# ArduSatPrototypingModule.net
KiCad netlist of a schematic drawn in EAGLE
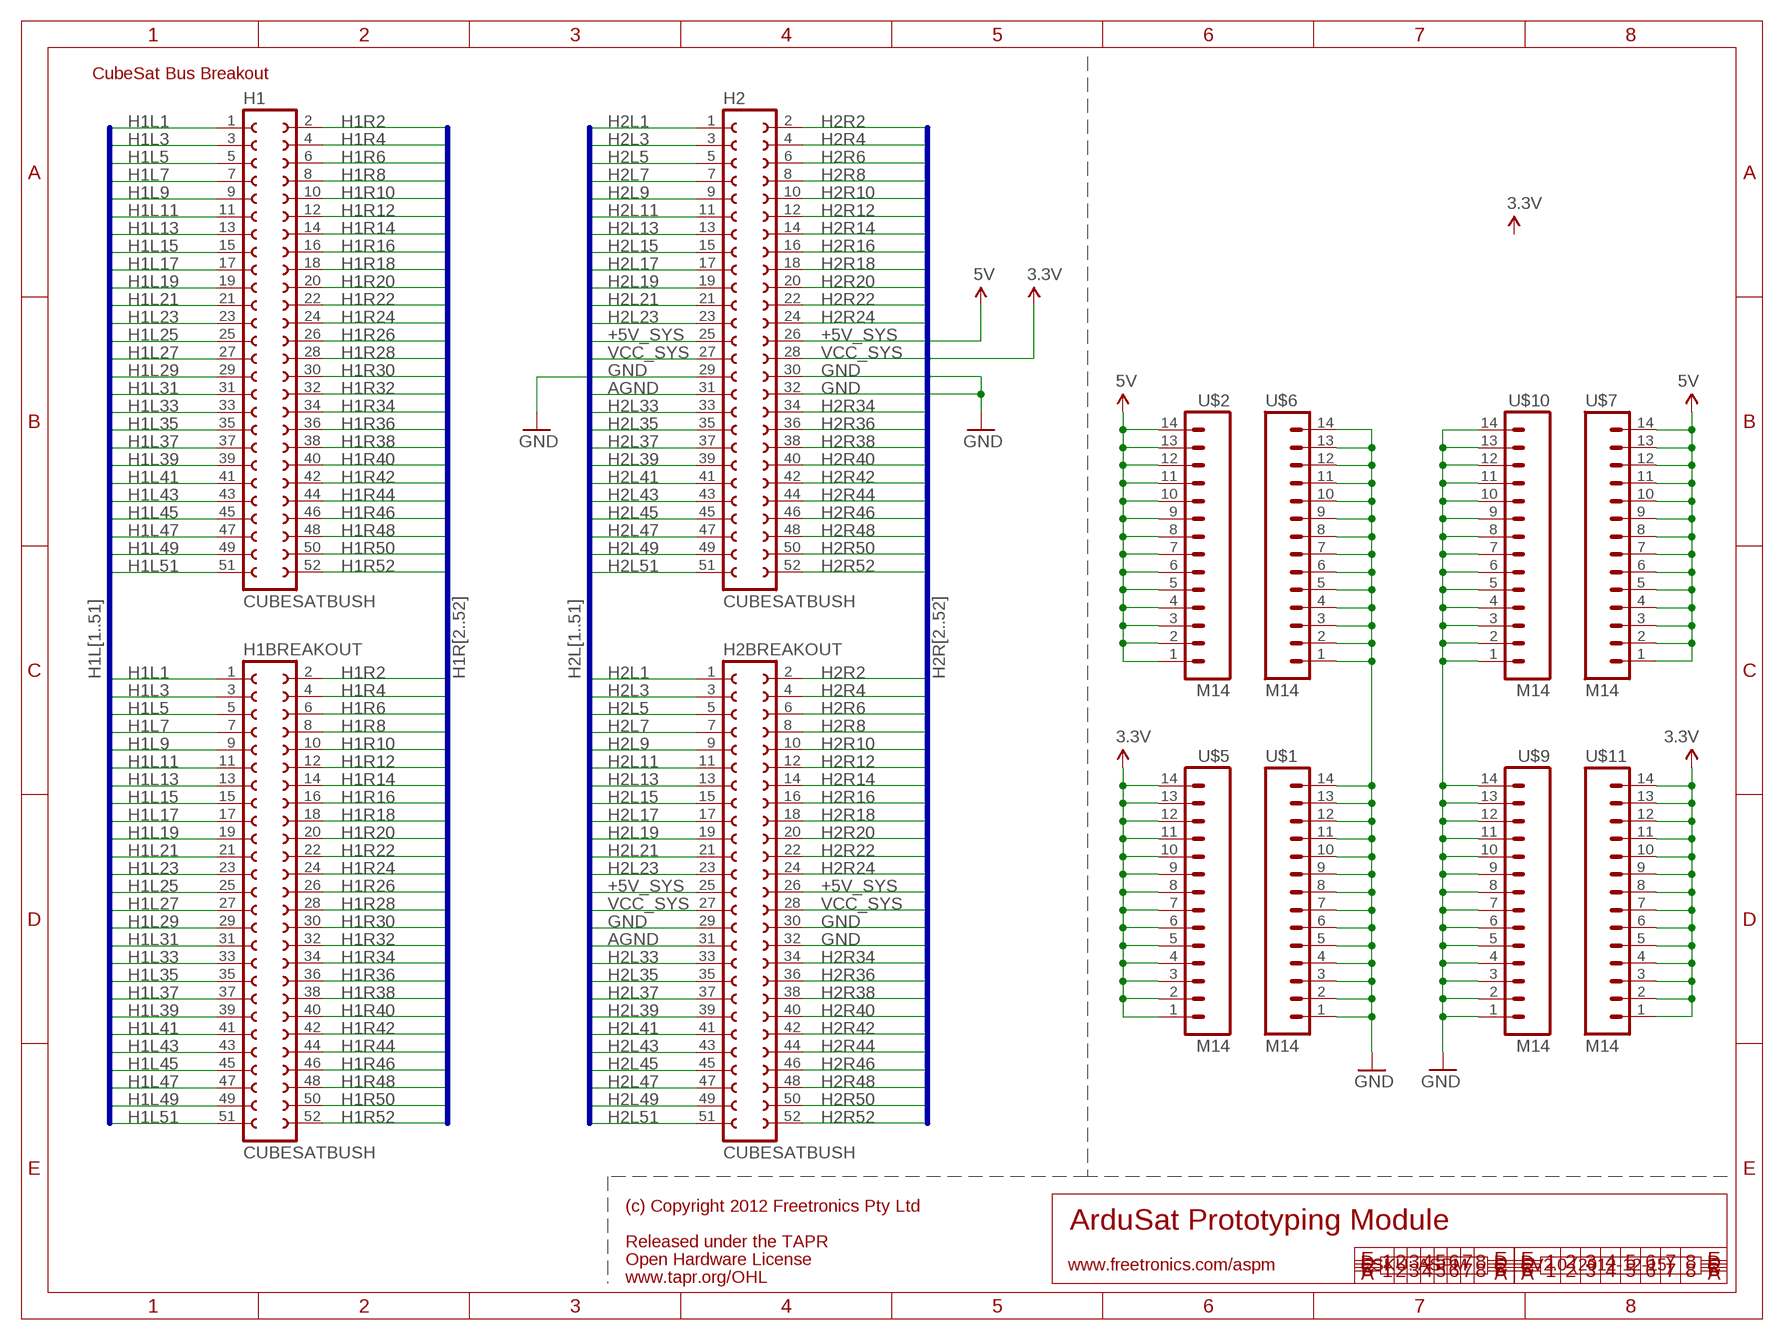
[diagram p0: schematic, sheet 1]

(export (version "E")
  (design (tool "Eeschema 10.0.6"))
  (components
    (comp (ref "H1")
      (value "CUBESATBUSH")
      (footprint "eagle-import:CUBESATBUS")
      (libsource (lib "eagle-import") (part "CUBESATBUSH"))
    )
    (comp (ref "H1BREAKOUT")
      (value "CUBESATBUSH")
      (footprint "eagle-import:CUBESATBUS")
      (libsource (lib "eagle-import") (part "CUBESATBUSH"))
    )
    (comp (ref "H2")
      (value "CUBESATBUSH")
      (footprint "eagle-import:CUBESATBUS")
      (libsource (lib "eagle-import") (part "CUBESATBUSH"))
    )
    (comp (ref "H2BREAKOUT")
      (value "CUBESATBUSH")
      (footprint "eagle-import:CUBESATBUS")
      (libsource (lib "eagle-import") (part "CUBESATBUSH"))
    )
    (comp (ref "U$1")
      (value "M14")
      (footprint "eagle-import:1X14")
      (libsource (lib "eagle-import") (part "M14"))
    )
    (comp (ref "U$2")
      (value "M14")
      (footprint "eagle-import:1X14")
      (libsource (lib "eagle-import") (part "M14"))
    )
    (comp (ref "U$5")
      (value "M14")
      (footprint "eagle-import:1X14")
      (libsource (lib "eagle-import") (part "M14"))
    )
    (comp (ref "U$6")
      (value "M14")
      (footprint "eagle-import:1X14")
      (libsource (lib "eagle-import") (part "M14"))
    )
    (comp (ref "U$7")
      (value "M14")
      (footprint "eagle-import:1X14")
      (libsource (lib "eagle-import") (part "M14"))
    )
    (comp (ref "U$9")
      (value "M14")
      (footprint "eagle-import:1X14")
      (libsource (lib "eagle-import") (part "M14"))
    )
    (comp (ref "U$10")
      (value "M14")
      (footprint "eagle-import:1X14")
      (libsource (lib "eagle-import") (part "M14"))
    )
    (comp (ref "U$11")
      (value "M14")
      (footprint "eagle-import:1X14")
      (libsource (lib "eagle-import") (part "M14"))
    )
  )
  (nets
    (net (code "109") (name "/AGND") (class "Default")
      (node (ref "H2") (pin "31") (pinfunction "31_31") (pintype "passive"))
      (node (ref "H2BREAKOUT") (pin "31") (pinfunction "31_31") (pintype "passive"))
    )
    (net (code "110") (name "/H1L1") (class "Default")
      (node (ref "H1") (pin "1") (pinfunction "1_1") (pintype "passive"))
      (node (ref "H1BREAKOUT") (pin "1") (pinfunction "1_1") (pintype "passive"))
    )
    (net (code "111") (name "/H1L3") (class "Default")
      (node (ref "H1") (pin "3") (pinfunction "3_3") (pintype "passive"))
      (node (ref "H1BREAKOUT") (pin "3") (pinfunction "3_3") (pintype "passive"))
    )
    (net (code "112") (name "/H1L5") (class "Default")
      (node (ref "H1") (pin "5") (pinfunction "5_5") (pintype "passive"))
      (node (ref "H1BREAKOUT") (pin "5") (pinfunction "5_5") (pintype "passive"))
    )
    (net (code "113") (name "/H1L7") (class "Default")
      (node (ref "H1") (pin "7") (pinfunction "7_7") (pintype "passive"))
      (node (ref "H1BREAKOUT") (pin "7") (pinfunction "7_7") (pintype "passive"))
    )
    (net (code "114") (name "/H1L9") (class "Default")
      (node (ref "H1") (pin "9") (pinfunction "9_9") (pintype "passive"))
      (node (ref "H1BREAKOUT") (pin "9") (pinfunction "9_9") (pintype "passive"))
    )
    (net (code "115") (name "/H1L11") (class "Default")
      (node (ref "H1") (pin "11") (pinfunction "11_11") (pintype "passive"))
      (node (ref "H1BREAKOUT") (pin "11") (pinfunction "11_11") (pintype "passive"))
    )
    (net (code "116") (name "/H1L13") (class "Default")
      (node (ref "H1") (pin "13") (pinfunction "13_13") (pintype "passive"))
      (node (ref "H1BREAKOUT") (pin "13") (pinfunction "13_13") (pintype "passive"))
    )
    (net (code "117") (name "/H1L15") (class "Default")
      (node (ref "H1") (pin "15") (pinfunction "15_15") (pintype "passive"))
      (node (ref "H1BREAKOUT") (pin "15") (pinfunction "15_15") (pintype "passive"))
    )
    (net (code "118") (name "/H1L17") (class "Default")
      (node (ref "H1") (pin "17") (pinfunction "17_17") (pintype "passive"))
      (node (ref "H1BREAKOUT") (pin "17") (pinfunction "17_17") (pintype "passive"))
    )
    (net (code "119") (name "/H1L19") (class "Default")
      (node (ref "H1") (pin "19") (pinfunction "19_19") (pintype "passive"))
      (node (ref "H1BREAKOUT") (pin "19") (pinfunction "19_19") (pintype "passive"))
    )
    (net (code "120") (name "/H1L21") (class "Default")
      (node (ref "H1") (pin "21") (pinfunction "21_21") (pintype "passive"))
      (node (ref "H1BREAKOUT") (pin "21") (pinfunction "21_21") (pintype "passive"))
    )
    (net (code "121") (name "/H1L23") (class "Default")
      (node (ref "H1") (pin "23") (pinfunction "23_23") (pintype "passive"))
      (node (ref "H1BREAKOUT") (pin "23") (pinfunction "23_23") (pintype "passive"))
    )
    (net (code "122") (name "/H1L25") (class "Default")
      (node (ref "H1") (pin "25") (pinfunction "25_25") (pintype "passive"))
      (node (ref "H1BREAKOUT") (pin "25") (pinfunction "25_25") (pintype "passive"))
    )
    (net (code "123") (name "/H1L27") (class "Default")
      (node (ref "H1") (pin "27") (pinfunction "27_27") (pintype "passive"))
      (node (ref "H1BREAKOUT") (pin "27") (pinfunction "27_27") (pintype "passive"))
    )
    (net (code "124") (name "/H1L29") (class "Default")
      (node (ref "H1") (pin "29") (pinfunction "29_29") (pintype "passive"))
      (node (ref "H1BREAKOUT") (pin "29") (pinfunction "29_29") (pintype "passive"))
    )
    (net (code "125") (name "/H1L31") (class "Default")
      (node (ref "H1") (pin "31") (pinfunction "31_31") (pintype "passive"))
      (node (ref "H1BREAKOUT") (pin "31") (pinfunction "31_31") (pintype "passive"))
    )
    (net (code "126") (name "/H1L33") (class "Default")
      (node (ref "H1") (pin "33") (pinfunction "33_33") (pintype "passive"))
      (node (ref "H1BREAKOUT") (pin "33") (pinfunction "33_33") (pintype "passive"))
    )
    (net (code "127") (name "/H1L35") (class "Default")
      (node (ref "H1") (pin "35") (pinfunction "35_35") (pintype "passive"))
      (node (ref "H1BREAKOUT") (pin "35") (pinfunction "35_35") (pintype "passive"))
    )
    (net (code "128") (name "/H1L37") (class "Default")
      (node (ref "H1") (pin "37") (pinfunction "37_37") (pintype "passive"))
      (node (ref "H1BREAKOUT") (pin "37") (pinfunction "37_37") (pintype "passive"))
    )
    (net (code "129") (name "/H1L39") (class "Default")
      (node (ref "H1") (pin "39") (pinfunction "39_39") (pintype "passive"))
      (node (ref "H1BREAKOUT") (pin "39") (pinfunction "39_39") (pintype "passive"))
    )
    (net (code "130") (name "/H1L41") (class "Default")
      (node (ref "H1") (pin "41") (pinfunction "41_41") (pintype "passive"))
      (node (ref "H1BREAKOUT") (pin "41") (pinfunction "41_41") (pintype "passive"))
    )
    (net (code "131") (name "/H1L43") (class "Default")
      (node (ref "H1") (pin "43") (pinfunction "43_43") (pintype "passive"))
      (node (ref "H1BREAKOUT") (pin "43") (pinfunction "43_43") (pintype "passive"))
    )
    (net (code "132") (name "/H1L45") (class "Default")
      (node (ref "H1") (pin "45") (pinfunction "45_45") (pintype "passive"))
      (node (ref "H1BREAKOUT") (pin "45") (pinfunction "45_45") (pintype "passive"))
    )
    (net (code "133") (name "/H1L47") (class "Default")
      (node (ref "H1") (pin "47") (pinfunction "47_47") (pintype "passive"))
      (node (ref "H1BREAKOUT") (pin "47") (pinfunction "47_47") (pintype "passive"))
    )
    (net (code "134") (name "/H1L49") (class "Default")
      (node (ref "H1") (pin "49") (pinfunction "49_49") (pintype "passive"))
      (node (ref "H1BREAKOUT") (pin "49") (pinfunction "49_49") (pintype "passive"))
    )
    (net (code "135") (name "/H1L51") (class "Default")
      (node (ref "H1") (pin "51") (pinfunction "51_51") (pintype "passive"))
      (node (ref "H1BREAKOUT") (pin "51") (pinfunction "51_51") (pintype "passive"))
    )
    (net (code "137") (name "/H1R2") (class "Default")
      (node (ref "H1") (pin "2") (pinfunction "2_2") (pintype "passive"))
      (node (ref "H1BREAKOUT") (pin "2") (pinfunction "2_2") (pintype "passive"))
    )
    (net (code "138") (name "/H1R4") (class "Default")
      (node (ref "H1") (pin "4") (pinfunction "4_4") (pintype "passive"))
      (node (ref "H1BREAKOUT") (pin "4") (pinfunction "4_4") (pintype "passive"))
    )
    (net (code "139") (name "/H1R6") (class "Default")
      (node (ref "H1") (pin "6") (pinfunction "6_6") (pintype "passive"))
      (node (ref "H1BREAKOUT") (pin "6") (pinfunction "6_6") (pintype "passive"))
    )
    (net (code "140") (name "/H1R8") (class "Default")
      (node (ref "H1") (pin "8") (pinfunction "8_8") (pintype "passive"))
      (node (ref "H1BREAKOUT") (pin "8") (pinfunction "8_8") (pintype "passive"))
    )
    (net (code "141") (name "/H1R10") (class "Default")
      (node (ref "H1") (pin "10") (pinfunction "10_10") (pintype "passive"))
      (node (ref "H1BREAKOUT") (pin "10") (pinfunction "10_10") (pintype "passive"))
    )
    (net (code "142") (name "/H1R12") (class "Default")
      (node (ref "H1") (pin "12") (pinfunction "12_12") (pintype "passive"))
      (node (ref "H1BREAKOUT") (pin "12") (pinfunction "12_12") (pintype "passive"))
    )
    (net (code "143") (name "/H1R14") (class "Default")
      (node (ref "H1") (pin "14") (pinfunction "14_14") (pintype "passive"))
      (node (ref "H1BREAKOUT") (pin "14") (pinfunction "14_14") (pintype "passive"))
    )
    (net (code "144") (name "/H1R16") (class "Default")
      (node (ref "H1") (pin "16") (pinfunction "16_16") (pintype "passive"))
      (node (ref "H1BREAKOUT") (pin "16") (pinfunction "16_16") (pintype "passive"))
    )
    (net (code "145") (name "/H1R18") (class "Default")
      (node (ref "H1") (pin "18") (pinfunction "18_18") (pintype "passive"))
      (node (ref "H1BREAKOUT") (pin "18") (pinfunction "18_18") (pintype "passive"))
    )
    (net (code "146") (name "/H1R20") (class "Default")
      (node (ref "H1") (pin "20") (pinfunction "20_20") (pintype "passive"))
      (node (ref "H1BREAKOUT") (pin "20") (pinfunction "20_20") (pintype "passive"))
    )
    (net (code "147") (name "/H1R22") (class "Default")
      (node (ref "H1") (pin "22") (pinfunction "22_22") (pintype "passive"))
      (node (ref "H1BREAKOUT") (pin "22") (pinfunction "22_22") (pintype "passive"))
    )
    (net (code "148") (name "/H1R24") (class "Default")
      (node (ref "H1") (pin "24") (pinfunction "24_24") (pintype "passive"))
      (node (ref "H1BREAKOUT") (pin "24") (pinfunction "24_24") (pintype "passive"))
    )
    (net (code "149") (name "/H1R26") (class "Default")
      (node (ref "H1") (pin "26") (pinfunction "26_26") (pintype "passive"))
      (node (ref "H1BREAKOUT") (pin "26") (pinfunction "26_26") (pintype "passive"))
    )
    (net (code "150") (name "/H1R28") (class "Default")
      (node (ref "H1") (pin "28") (pinfunction "28_28") (pintype "passive"))
      (node (ref "H1BREAKOUT") (pin "28") (pinfunction "28_28") (pintype "passive"))
    )
    (net (code "151") (name "/H1R30") (class "Default")
      (node (ref "H1") (pin "30") (pinfunction "30_30") (pintype "passive"))
      (node (ref "H1BREAKOUT") (pin "30") (pinfunction "30_30") (pintype "passive"))
    )
    (net (code "152") (name "/H1R32") (class "Default")
      (node (ref "H1") (pin "32") (pinfunction "32_32") (pintype "passive"))
      (node (ref "H1BREAKOUT") (pin "32") (pinfunction "32_32") (pintype "passive"))
    )
    (net (code "153") (name "/H1R34") (class "Default")
      (node (ref "H1") (pin "34") (pinfunction "34_34") (pintype "passive"))
      (node (ref "H1BREAKOUT") (pin "34") (pinfunction "34_34") (pintype "passive"))
    )
    (net (code "154") (name "/H1R36") (class "Default")
      (node (ref "H1") (pin "36") (pinfunction "36_36") (pintype "passive"))
      (node (ref "H1BREAKOUT") (pin "36") (pinfunction "36_36") (pintype "passive"))
    )
    (net (code "155") (name "/H1R38") (class "Default")
      (node (ref "H1") (pin "38") (pinfunction "38_38") (pintype "passive"))
      (node (ref "H1BREAKOUT") (pin "38") (pinfunction "38_38") (pintype "passive"))
    )
    (net (code "156") (name "/H1R40") (class "Default")
      (node (ref "H1") (pin "40") (pinfunction "40_40") (pintype "passive"))
      (node (ref "H1BREAKOUT") (pin "40") (pinfunction "40_40") (pintype "passive"))
    )
    (net (code "157") (name "/H1R42") (class "Default")
      (node (ref "H1") (pin "42") (pinfunction "42_42") (pintype "passive"))
      (node (ref "H1BREAKOUT") (pin "42") (pinfunction "42_42") (pintype "passive"))
    )
    (net (code "158") (name "/H1R44") (class "Default")
      (node (ref "H1") (pin "44") (pinfunction "44_44") (pintype "passive"))
      (node (ref "H1BREAKOUT") (pin "44") (pinfunction "44_44") (pintype "passive"))
    )
    (net (code "159") (name "/H1R46") (class "Default")
      (node (ref "H1") (pin "46") (pinfunction "46_46") (pintype "passive"))
      (node (ref "H1BREAKOUT") (pin "46") (pinfunction "46_46") (pintype "passive"))
    )
    (net (code "160") (name "/H1R48") (class "Default")
      (node (ref "H1") (pin "48") (pinfunction "48_48") (pintype "passive"))
      (node (ref "H1BREAKOUT") (pin "48") (pinfunction "48_48") (pintype "passive"))
    )
    (net (code "161") (name "/H1R50") (class "Default")
      (node (ref "H1") (pin "50") (pinfunction "50_50") (pintype "passive"))
      (node (ref "H1BREAKOUT") (pin "50") (pinfunction "50_50") (pintype "passive"))
    )
    (net (code "162") (name "/H1R52") (class "Default")
      (node (ref "H1") (pin "52") (pinfunction "52_52") (pintype "passive"))
      (node (ref "H1BREAKOUT") (pin "52") (pinfunction "52_52") (pintype "passive"))
    )
    (net (code "164") (name "/H2L1") (class "Default")
      (node (ref "H2") (pin "1") (pinfunction "1_1") (pintype "passive"))
      (node (ref "H2BREAKOUT") (pin "1") (pinfunction "1_1") (pintype "passive"))
    )
    (net (code "165") (name "/H2L3") (class "Default")
      (node (ref "H2") (pin "3") (pinfunction "3_3") (pintype "passive"))
      (node (ref "H2BREAKOUT") (pin "3") (pinfunction "3_3") (pintype "passive"))
    )
    (net (code "166") (name "/H2L5") (class "Default")
      (node (ref "H2") (pin "5") (pinfunction "5_5") (pintype "passive"))
      (node (ref "H2BREAKOUT") (pin "5") (pinfunction "5_5") (pintype "passive"))
    )
    (net (code "167") (name "/H2L7") (class "Default")
      (node (ref "H2") (pin "7") (pinfunction "7_7") (pintype "passive"))
      (node (ref "H2BREAKOUT") (pin "7") (pinfunction "7_7") (pintype "passive"))
    )
    (net (code "168") (name "/H2L9") (class "Default")
      (node (ref "H2") (pin "9") (pinfunction "9_9") (pintype "passive"))
      (node (ref "H2BREAKOUT") (pin "9") (pinfunction "9_9") (pintype "passive"))
    )
    (net (code "169") (name "/H2L11") (class "Default")
      (node (ref "H2") (pin "11") (pinfunction "11_11") (pintype "passive"))
      (node (ref "H2BREAKOUT") (pin "11") (pinfunction "11_11") (pintype "passive"))
    )
    (net (code "170") (name "/H2L13") (class "Default")
      (node (ref "H2") (pin "13") (pinfunction "13_13") (pintype "passive"))
      (node (ref "H2BREAKOUT") (pin "13") (pinfunction "13_13") (pintype "passive"))
    )
    (net (code "171") (name "/H2L15") (class "Default")
      (node (ref "H2") (pin "15") (pinfunction "15_15") (pintype "passive"))
      (node (ref "H2BREAKOUT") (pin "15") (pinfunction "15_15") (pintype "passive"))
    )
    (net (code "172") (name "/H2L17") (class "Default")
      (node (ref "H2") (pin "17") (pinfunction "17_17") (pintype "passive"))
      (node (ref "H2BREAKOUT") (pin "17") (pinfunction "17_17") (pintype "passive"))
    )
    (net (code "173") (name "/H2L19") (class "Default")
      (node (ref "H2") (pin "19") (pinfunction "19_19") (pintype "passive"))
      (node (ref "H2BREAKOUT") (pin "19") (pinfunction "19_19") (pintype "passive"))
    )
    (net (code "174") (name "/H2L21") (class "Default")
      (node (ref "H2") (pin "21") (pinfunction "21_21") (pintype "passive"))
      (node (ref "H2BREAKOUT") (pin "21") (pinfunction "21_21") (pintype "passive"))
    )
    (net (code "175") (name "/H2L23") (class "Default")
      (node (ref "H2") (pin "23") (pinfunction "23_23") (pintype "passive"))
      (node (ref "H2BREAKOUT") (pin "23") (pinfunction "23_23") (pintype "passive"))
    )
    (net (code "176") (name "/H2L33") (class "Default")
      (node (ref "H2") (pin "33") (pinfunction "33_33") (pintype "passive"))
      (node (ref "H2BREAKOUT") (pin "33") (pinfunction "33_33") (pintype "passive"))
    )
    (net (code "177") (name "/H2L35") (class "Default")
      (node (ref "H2") (pin "35") (pinfunction "35_35") (pintype "passive"))
      (node (ref "H2BREAKOUT") (pin "35") (pinfunction "35_35") (pintype "passive"))
    )
    (net (code "178") (name "/H2L37") (class "Default")
      (node (ref "H2") (pin "37") (pinfunction "37_37") (pintype "passive"))
      (node (ref "H2BREAKOUT") (pin "37") (pinfunction "37_37") (pintype "passive"))
    )
    (net (code "179") (name "/H2L39") (class "Default")
      (node (ref "H2") (pin "39") (pinfunction "39_39") (pintype "passive"))
      (node (ref "H2BREAKOUT") (pin "39") (pinfunction "39_39") (pintype "passive"))
    )
    (net (code "180") (name "/H2L41") (class "Default")
      (node (ref "H2") (pin "41") (pinfunction "41_41") (pintype "passive"))
      (node (ref "H2BREAKOUT") (pin "41") (pinfunction "41_41") (pintype "passive"))
    )
    (net (code "181") (name "/H2L43") (class "Default")
      (node (ref "H2") (pin "43") (pinfunction "43_43") (pintype "passive"))
      (node (ref "H2BREAKOUT") (pin "43") (pinfunction "43_43") (pintype "passive"))
    )
    (net (code "182") (name "/H2L45") (class "Default")
      (node (ref "H2") (pin "45") (pinfunction "45_45") (pintype "passive"))
      (node (ref "H2BREAKOUT") (pin "45") (pinfunction "45_45") (pintype "passive"))
    )
    (net (code "183") (name "/H2L47") (class "Default")
      (node (ref "H2") (pin "47") (pinfunction "47_47") (pintype "passive"))
      (node (ref "H2BREAKOUT") (pin "47") (pinfunction "47_47") (pintype "passive"))
    )
    (net (code "184") (name "/H2L49") (class "Default")
      (node (ref "H2") (pin "49") (pinfunction "49_49") (pintype "passive"))
      (node (ref "H2BREAKOUT") (pin "49") (pinfunction "49_49") (pintype "passive"))
    )
    (net (code "185") (name "/H2L51") (class "Default")
      (node (ref "H2") (pin "51") (pinfunction "51_51") (pintype "passive"))
      (node (ref "H2BREAKOUT") (pin "51") (pinfunction "51_51") (pintype "passive"))
    )
    (net (code "187") (name "/H2R2") (class "Default")
      (node (ref "H2") (pin "2") (pinfunction "2_2") (pintype "passive"))
      (node (ref "H2BREAKOUT") (pin "2") (pinfunction "2_2") (pintype "passive"))
    )
    (net (code "188") (name "/H2R4") (class "Default")
      (node (ref "H2") (pin "4") (pinfunction "4_4") (pintype "passive"))
      (node (ref "H2BREAKOUT") (pin "4") (pinfunction "4_4") (pintype "passive"))
    )
    (net (code "189") (name "/H2R6") (class "Default")
      (node (ref "H2") (pin "6") (pinfunction "6_6") (pintype "passive"))
      (node (ref "H2BREAKOUT") (pin "6") (pinfunction "6_6") (pintype "passive"))
    )
    (net (code "190") (name "/H2R8") (class "Default")
      (node (ref "H2") (pin "8") (pinfunction "8_8") (pintype "passive"))
      (node (ref "H2BREAKOUT") (pin "8") (pinfunction "8_8") (pintype "passive"))
    )
    (net (code "191") (name "/H2R10") (class "Default")
      (node (ref "H2") (pin "10") (pinfunction "10_10") (pintype "passive"))
      (node (ref "H2BREAKOUT") (pin "10") (pinfunction "10_10") (pintype "passive"))
    )
    (net (code "192") (name "/H2R12") (class "Default")
      (node (ref "H2") (pin "12") (pinfunction "12_12") (pintype "passive"))
      (node (ref "H2BREAKOUT") (pin "12") (pinfunction "12_12") (pintype "passive"))
    )
    (net (code "193") (name "/H2R14") (class "Default")
      (node (ref "H2") (pin "14") (pinfunction "14_14") (pintype "passive"))
      (node (ref "H2BREAKOUT") (pin "14") (pinfunction "14_14") (pintype "passive"))
    )
    (net (code "194") (name "/H2R16") (class "Default")
      (node (ref "H2") (pin "16") (pinfunction "16_16") (pintype "passive"))
      (node (ref "H2BREAKOUT") (pin "16") (pinfunction "16_16") (pintype "passive"))
    )
    (net (code "195") (name "/H2R18") (class "Default")
      (node (ref "H2") (pin "18") (pinfunction "18_18") (pintype "passive"))
      (node (ref "H2BREAKOUT") (pin "18") (pinfunction "18_18") (pintype "passive"))
    )
    (net (code "196") (name "/H2R20") (class "Default")
      (node (ref "H2") (pin "20") (pinfunction "20_20") (pintype "passive"))
      (node (ref "H2BREAKOUT") (pin "20") (pinfunction "20_20") (pintype "passive"))
    )
    (net (code "197") (name "/H2R22") (class "Default")
      (node (ref "H2") (pin "22") (pinfunction "22_22") (pintype "passive"))
      (node (ref "H2BREAKOUT") (pin "22") (pinfunction "22_22") (pintype "passive"))
    )
    (net (code "198") (name "/H2R24") (class "Default")
      (node (ref "H2") (pin "24") (pinfunction "24_24") (pintype "passive"))
      (node (ref "H2BREAKOUT") (pin "24") (pinfunction "24_24") (pintype "passive"))
    )
    (net (code "199") (name "/H2R34") (class "Default")
      (node (ref "H2") (pin "34") (pinfunction "34_34") (pintype "passive"))
      (node (ref "H2BREAKOUT") (pin "34") (pinfunction "34_34") (pintype "passive"))
    )
    (net (code "200") (name "/H2R36") (class "Default")
      (node (ref "H2") (pin "36") (pinfunction "36_36") (pintype "passive"))
      (node (ref "H2BREAKOUT") (pin "36") (pinfunction "36_36") (pintype "passive"))
    )
    (net (code "201") (name "/H2R38") (class "Default")
      (node (ref "H2") (pin "38") (pinfunction "38_38") (pintype "passive"))
      (node (ref "H2BREAKOUT") (pin "38") (pinfunction "38_38") (pintype "passive"))
    )
    (net (code "202") (name "/H2R40") (class "Default")
      (node (ref "H2") (pin "40") (pinfunction "40_40") (pintype "passive"))
      (node (ref "H2BREAKOUT") (pin "40") (pinfunction "40_40") (pintype "passive"))
    )
    (net (code "203") (name "/H2R42") (class "Default")
      (node (ref "H2") (pin "42") (pinfunction "42_42") (pintype "passive"))
      (node (ref "H2BREAKOUT") (pin "42") (pinfunction "42_42") (pintype "passive"))
    )
    (net (code "204") (name "/H2R44") (class "Default")
      (node (ref "H2") (pin "44") (pinfunction "44_44") (pintype "passive"))
      (node (ref "H2BREAKOUT") (pin "44") (pinfunction "44_44") (pintype "passive"))
    )
    (net (code "205") (name "/H2R46") (class "Default")
      (node (ref "H2") (pin "46") (pinfunction "46_46") (pintype "passive"))
      (node (ref "H2BREAKOUT") (pin "46") (pinfunction "46_46") (pintype "passive"))
    )
    (net (code "206") (name "/H2R48") (class "Default")
      (node (ref "H2") (pin "48") (pinfunction "48_48") (pintype "passive"))
      (node (ref "H2BREAKOUT") (pin "48") (pinfunction "48_48") (pintype "passive"))
    )
    (net (code "207") (name "/H2R50") (class "Default")
      (node (ref "H2") (pin "50") (pinfunction "50_50") (pintype "passive"))
      (node (ref "H2BREAKOUT") (pin "50") (pinfunction "50_50") (pintype "passive"))
    )
    (net (code "208") (name "/H2R52") (class "Default")
      (node (ref "H2") (pin "52") (pinfunction "52_52") (pintype "passive"))
      (node (ref "H2BREAKOUT") (pin "52") (pinfunction "52_52") (pintype "passive"))
    )
    (net (code "210") (name "3.3V") (class "Default")
      (node (ref "H2") (pin "27") (pinfunction "27_27") (pintype "passive"))
      (node (ref "H2") (pin "28") (pinfunction "28_28") (pintype "passive"))
      (node (ref "H2BREAKOUT") (pin "27") (pinfunction "27_27") (pintype "passive"))
      (node (ref "H2BREAKOUT") (pin "28") (pinfunction "28_28") (pintype "passive"))
      (node (ref "U$11") (pin "1") (pinfunction "1_1") (pintype "passive"))
      (node (ref "U$11") (pin "10") (pinfunction "10_10") (pintype "passive"))
      (node (ref "U$11") (pin "11") (pinfunction "11_11") (pintype "passive"))
      (node (ref "U$11") (pin "12") (pinfunction "12_12") (pintype "passive"))
      (node (ref "U$11") (pin "13") (pinfunction "13_13") (pintype "passive"))
      (node (ref "U$11") (pin "14") (pinfunction "14_14") (pintype "passive"))
      (node (ref "U$11") (pin "2") (pinfunction "2_2") (pintype "passive"))
      (node (ref "U$11") (pin "3") (pinfunction "3_3") (pintype "passive"))
      (node (ref "U$11") (pin "4") (pinfunction "4_4") (pintype "passive"))
      (node (ref "U$11") (pin "5") (pinfunction "5_5") (pintype "passive"))
      (node (ref "U$11") (pin "6") (pinfunction "6_6") (pintype "passive"))
      (node (ref "U$11") (pin "7") (pinfunction "7_7") (pintype "passive"))
      (node (ref "U$11") (pin "8") (pinfunction "8_8") (pintype "passive"))
      (node (ref "U$11") (pin "9") (pinfunction "9_9") (pintype "passive"))
      (node (ref "U$5") (pin "1") (pinfunction "1_1") (pintype "passive"))
      (node (ref "U$5") (pin "10") (pinfunction "10_10") (pintype "passive"))
      (node (ref "U$5") (pin "11") (pinfunction "11_11") (pintype "passive"))
      (node (ref "U$5") (pin "12") (pinfunction "12_12") (pintype "passive"))
      (node (ref "U$5") (pin "13") (pinfunction "13_13") (pintype "passive"))
      (node (ref "U$5") (pin "14") (pinfunction "14_14") (pintype "passive"))
      (node (ref "U$5") (pin "2") (pinfunction "2_2") (pintype "passive"))
      (node (ref "U$5") (pin "3") (pinfunction "3_3") (pintype "passive"))
      (node (ref "U$5") (pin "4") (pinfunction "4_4") (pintype "passive"))
      (node (ref "U$5") (pin "5") (pinfunction "5_5") (pintype "passive"))
      (node (ref "U$5") (pin "6") (pinfunction "6_6") (pintype "passive"))
      (node (ref "U$5") (pin "7") (pinfunction "7_7") (pintype "passive"))
      (node (ref "U$5") (pin "8") (pinfunction "8_8") (pintype "passive"))
      (node (ref "U$5") (pin "9") (pinfunction "9_9") (pintype "passive"))
    )
    (net (code "211") (name "5V") (class "Default")
      (node (ref "H2") (pin "25") (pinfunction "25_25") (pintype "passive"))
      (node (ref "H2") (pin "26") (pinfunction "26_26") (pintype "passive"))
      (node (ref "H2BREAKOUT") (pin "25") (pinfunction "25_25") (pintype "passive"))
      (node (ref "H2BREAKOUT") (pin "26") (pinfunction "26_26") (pintype "passive"))
      (node (ref "U$2") (pin "1") (pinfunction "1_1") (pintype "passive"))
      (node (ref "U$2") (pin "10") (pinfunction "10_10") (pintype "passive"))
      (node (ref "U$2") (pin "11") (pinfunction "11_11") (pintype "passive"))
      (node (ref "U$2") (pin "12") (pinfunction "12_12") (pintype "passive"))
      (node (ref "U$2") (pin "13") (pinfunction "13_13") (pintype "passive"))
      (node (ref "U$2") (pin "14") (pinfunction "14_14") (pintype "passive"))
      (node (ref "U$2") (pin "2") (pinfunction "2_2") (pintype "passive"))
      (node (ref "U$2") (pin "3") (pinfunction "3_3") (pintype "passive"))
      (node (ref "U$2") (pin "4") (pinfunction "4_4") (pintype "passive"))
      (node (ref "U$2") (pin "5") (pinfunction "5_5") (pintype "passive"))
      (node (ref "U$2") (pin "6") (pinfunction "6_6") (pintype "passive"))
      (node (ref "U$2") (pin "7") (pinfunction "7_7") (pintype "passive"))
      (node (ref "U$2") (pin "8") (pinfunction "8_8") (pintype "passive"))
      (node (ref "U$2") (pin "9") (pinfunction "9_9") (pintype "passive"))
      (node (ref "U$7") (pin "1") (pinfunction "1_1") (pintype "passive"))
      (node (ref "U$7") (pin "10") (pinfunction "10_10") (pintype "passive"))
      (node (ref "U$7") (pin "11") (pinfunction "11_11") (pintype "passive"))
      (node (ref "U$7") (pin "12") (pinfunction "12_12") (pintype "passive"))
      (node (ref "U$7") (pin "13") (pinfunction "13_13") (pintype "passive"))
      (node (ref "U$7") (pin "14") (pinfunction "14_14") (pintype "passive"))
      (node (ref "U$7") (pin "2") (pinfunction "2_2") (pintype "passive"))
      (node (ref "U$7") (pin "3") (pinfunction "3_3") (pintype "passive"))
      (node (ref "U$7") (pin "4") (pinfunction "4_4") (pintype "passive"))
      (node (ref "U$7") (pin "5") (pinfunction "5_5") (pintype "passive"))
      (node (ref "U$7") (pin "6") (pinfunction "6_6") (pintype "passive"))
      (node (ref "U$7") (pin "7") (pinfunction "7_7") (pintype "passive"))
      (node (ref "U$7") (pin "8") (pinfunction "8_8") (pintype "passive"))
      (node (ref "U$7") (pin "9") (pinfunction "9_9") (pintype "passive"))
    )
    (net (code "212") (name "GND") (class "Default")
      (node (ref "H2") (pin "29") (pinfunction "29_29") (pintype "passive"))
      (node (ref "H2") (pin "30") (pinfunction "30_30") (pintype "passive"))
      (node (ref "H2") (pin "32") (pinfunction "32_32") (pintype "passive"))
      (node (ref "H2BREAKOUT") (pin "29") (pinfunction "29_29") (pintype "passive"))
      (node (ref "H2BREAKOUT") (pin "30") (pinfunction "30_30") (pintype "passive"))
      (node (ref "H2BREAKOUT") (pin "32") (pinfunction "32_32") (pintype "passive"))
      (node (ref "U$1") (pin "1") (pinfunction "1_1") (pintype "passive"))
      (node (ref "U$1") (pin "10") (pinfunction "10_10") (pintype "passive"))
      (node (ref "U$1") (pin "11") (pinfunction "11_11") (pintype "passive"))
      (node (ref "U$1") (pin "12") (pinfunction "12_12") (pintype "passive"))
      (node (ref "U$1") (pin "13") (pinfunction "13_13") (pintype "passive"))
      (node (ref "U$1") (pin "14") (pinfunction "14_14") (pintype "passive"))
      (node (ref "U$1") (pin "2") (pinfunction "2_2") (pintype "passive"))
      (node (ref "U$1") (pin "3") (pinfunction "3_3") (pintype "passive"))
      (node (ref "U$1") (pin "4") (pinfunction "4_4") (pintype "passive"))
      (node (ref "U$1") (pin "5") (pinfunction "5_5") (pintype "passive"))
      (node (ref "U$1") (pin "6") (pinfunction "6_6") (pintype "passive"))
      (node (ref "U$1") (pin "7") (pinfunction "7_7") (pintype "passive"))
      (node (ref "U$1") (pin "8") (pinfunction "8_8") (pintype "passive"))
      (node (ref "U$1") (pin "9") (pinfunction "9_9") (pintype "passive"))
      (node (ref "U$10") (pin "1") (pinfunction "1_1") (pintype "passive"))
      (node (ref "U$10") (pin "10") (pinfunction "10_10") (pintype "passive"))
      (node (ref "U$10") (pin "11") (pinfunction "11_11") (pintype "passive"))
      (node (ref "U$10") (pin "12") (pinfunction "12_12") (pintype "passive"))
      (node (ref "U$10") (pin "13") (pinfunction "13_13") (pintype "passive"))
      (node (ref "U$10") (pin "14") (pinfunction "14_14") (pintype "passive"))
      (node (ref "U$10") (pin "2") (pinfunction "2_2") (pintype "passive"))
      (node (ref "U$10") (pin "3") (pinfunction "3_3") (pintype "passive"))
      (node (ref "U$10") (pin "4") (pinfunction "4_4") (pintype "passive"))
      (node (ref "U$10") (pin "5") (pinfunction "5_5") (pintype "passive"))
      (node (ref "U$10") (pin "6") (pinfunction "6_6") (pintype "passive"))
      (node (ref "U$10") (pin "7") (pinfunction "7_7") (pintype "passive"))
      (node (ref "U$10") (pin "8") (pinfunction "8_8") (pintype "passive"))
      (node (ref "U$10") (pin "9") (pinfunction "9_9") (pintype "passive"))
      (node (ref "U$6") (pin "1") (pinfunction "1_1") (pintype "passive"))
      (node (ref "U$6") (pin "10") (pinfunction "10_10") (pintype "passive"))
      (node (ref "U$6") (pin "11") (pinfunction "11_11") (pintype "passive"))
      (node (ref "U$6") (pin "12") (pinfunction "12_12") (pintype "passive"))
      (node (ref "U$6") (pin "13") (pinfunction "13_13") (pintype "passive"))
      (node (ref "U$6") (pin "14") (pinfunction "14_14") (pintype "passive"))
      (node (ref "U$6") (pin "2") (pinfunction "2_2") (pintype "passive"))
      (node (ref "U$6") (pin "3") (pinfunction "3_3") (pintype "passive"))
      (node (ref "U$6") (pin "4") (pinfunction "4_4") (pintype "passive"))
      (node (ref "U$6") (pin "5") (pinfunction "5_5") (pintype "passive"))
      (node (ref "U$6") (pin "6") (pinfunction "6_6") (pintype "passive"))
      (node (ref "U$6") (pin "7") (pinfunction "7_7") (pintype "passive"))
      (node (ref "U$6") (pin "8") (pinfunction "8_8") (pintype "passive"))
      (node (ref "U$6") (pin "9") (pinfunction "9_9") (pintype "passive"))
      (node (ref "U$9") (pin "1") (pinfunction "1_1") (pintype "passive"))
      (node (ref "U$9") (pin "10") (pinfunction "10_10") (pintype "passive"))
      (node (ref "U$9") (pin "11") (pinfunction "11_11") (pintype "passive"))
      (node (ref "U$9") (pin "12") (pinfunction "12_12") (pintype "passive"))
      (node (ref "U$9") (pin "13") (pinfunction "13_13") (pintype "passive"))
      (node (ref "U$9") (pin "14") (pinfunction "14_14") (pintype "passive"))
      (node (ref "U$9") (pin "2") (pinfunction "2_2") (pintype "passive"))
      (node (ref "U$9") (pin "3") (pinfunction "3_3") (pintype "passive"))
      (node (ref "U$9") (pin "4") (pinfunction "4_4") (pintype "passive"))
      (node (ref "U$9") (pin "5") (pinfunction "5_5") (pintype "passive"))
      (node (ref "U$9") (pin "6") (pinfunction "6_6") (pintype "passive"))
      (node (ref "U$9") (pin "7") (pinfunction "7_7") (pintype "passive"))
      (node (ref "U$9") (pin "8") (pinfunction "8_8") (pintype "passive"))
      (node (ref "U$9") (pin "9") (pinfunction "9_9") (pintype "passive"))
    )
  )
)
